# Sensors.net
KiCad netlist of a schematic drawn in Altium Designer
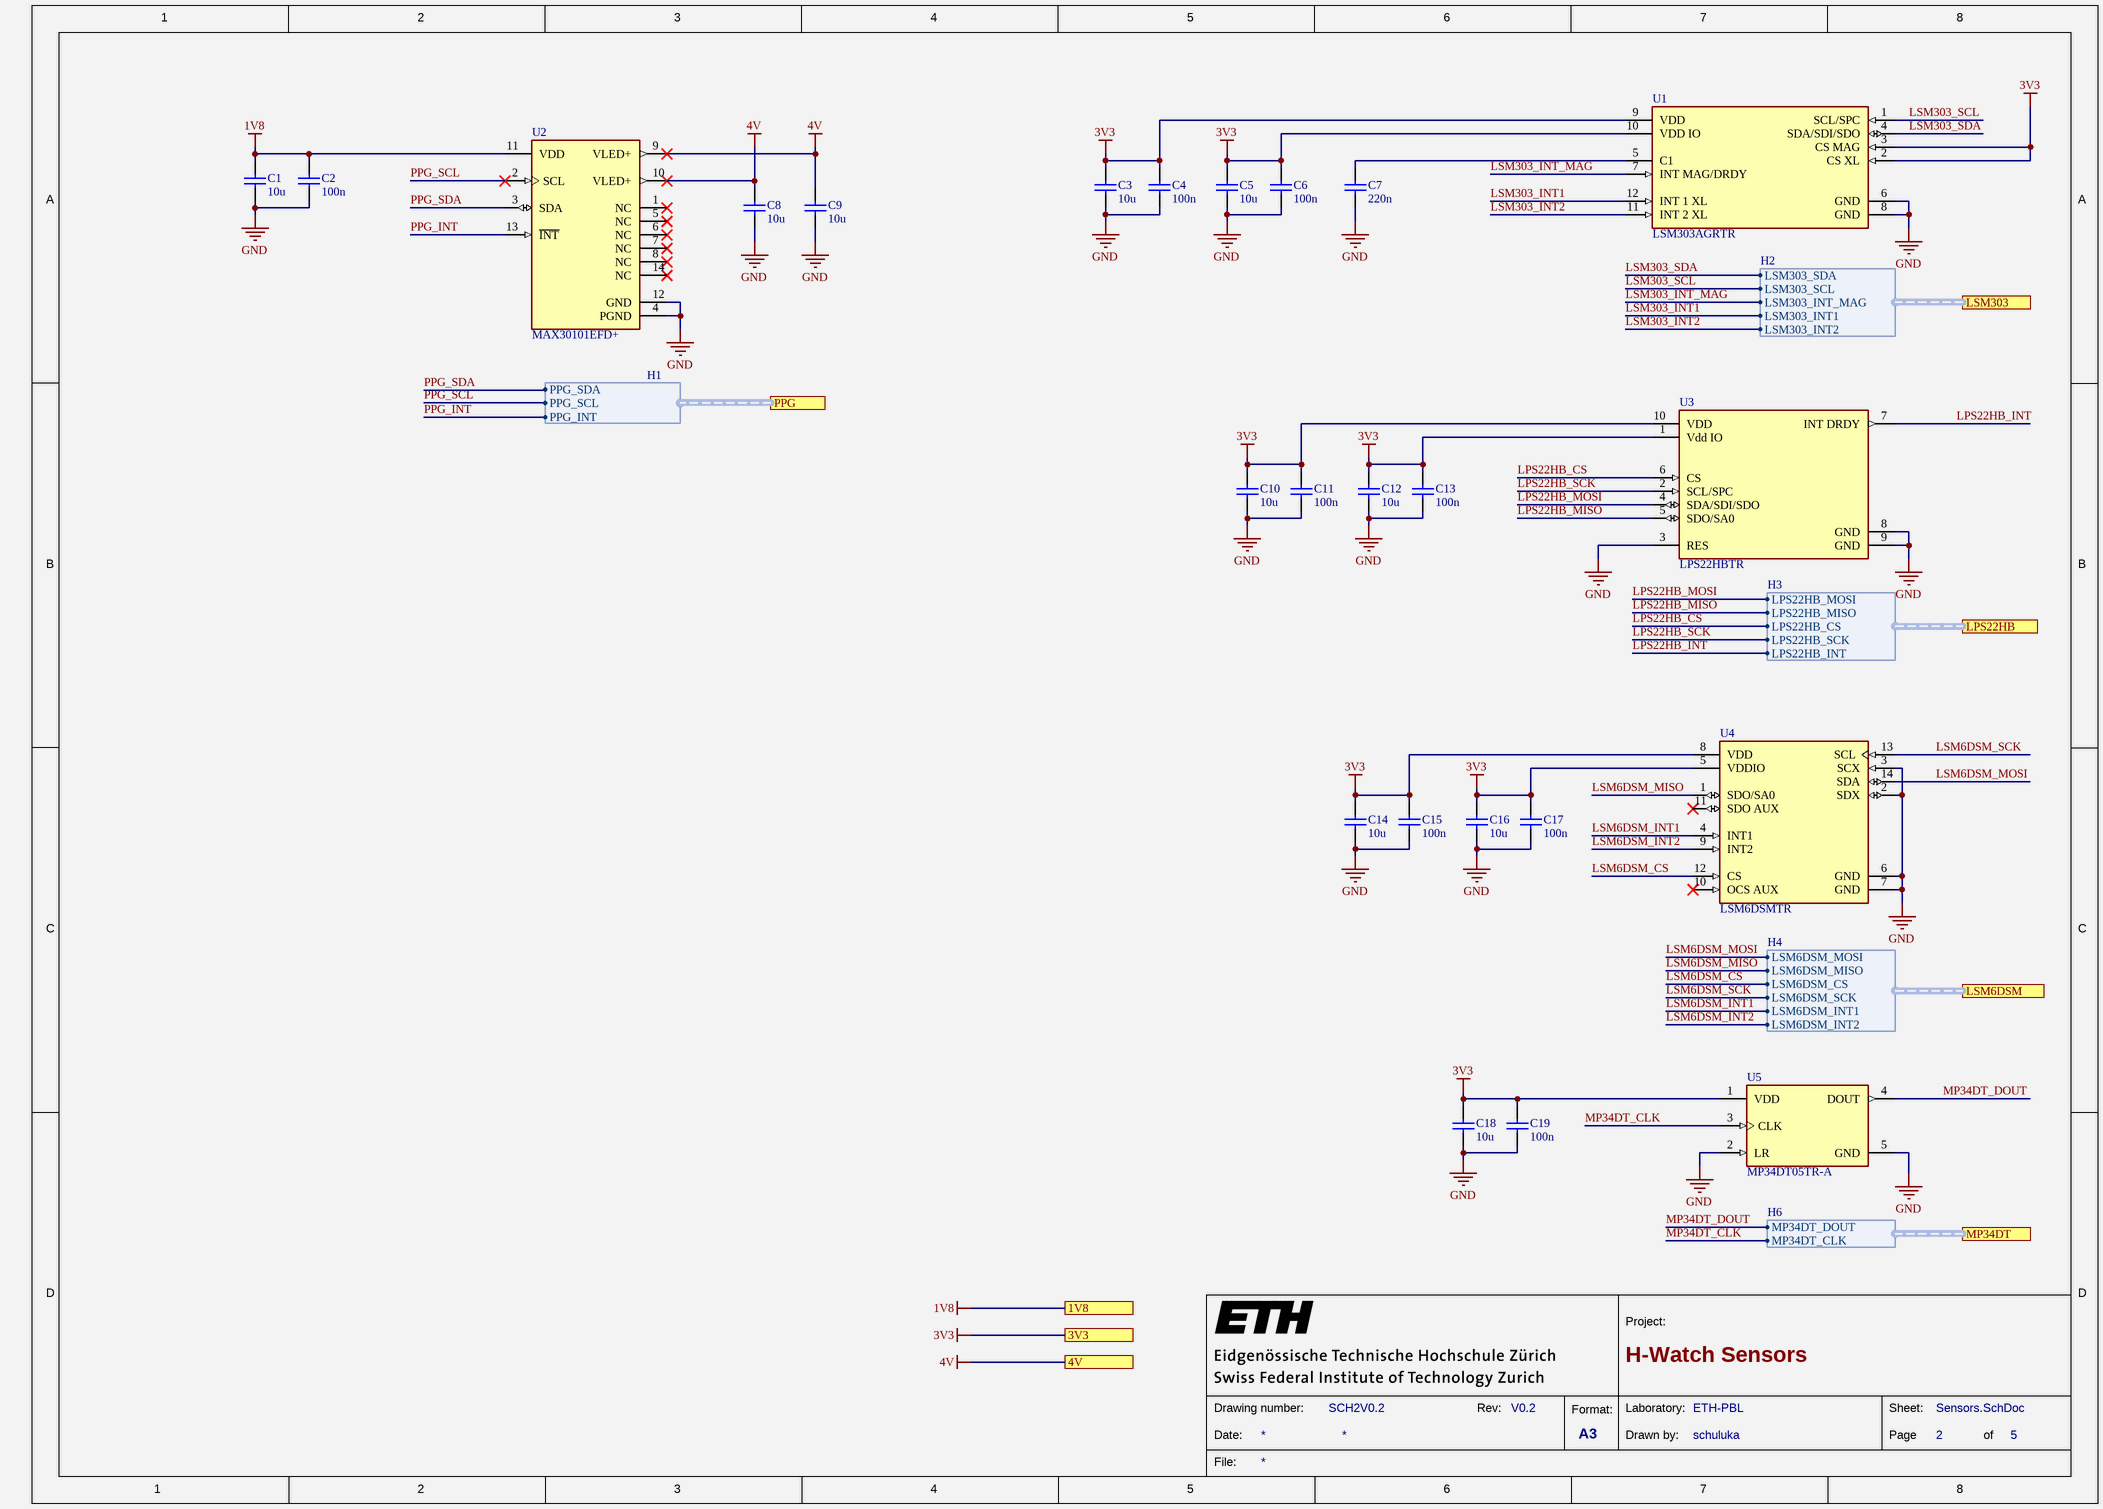
[diagram p0: Sensors.SchDoc]

(export (version "E")
  (design (tool "Eeschema 10.0.6"))
  (components
    (comp (ref "C1")
      (value "10u")
      (footprint "CAPC1005X70X10NL05")
      (description "Chip Capacitor, 10 uF, +/- 20%, -55 to 85 degC, 0402 (1005 Metric), RoHS, Tape and Reel")
      (fields
        (field (name "PCN PART NUMBER") "MLCCPartNumberChange30/Nov/2012")
        (field (name "TOLERANCE") "±20%")
      )
      (libsource (lib "Altium Content Vault") (part "CAP-NP-2"))
    )
    (comp (ref "C2")
      (value "100n")
      (footprint "CAPC1005X60X30ML05T10")
      (fields (field (name "MANUFACTURER") "Kemet") (field (name "PART NUMBER") "C0402C104K8PACTU"))
      (libsource (lib "Altium Content Vault") (part "CAP"))
    )
    (comp (ref "C3")
      (value "10u")
      (footprint "CAPC1005X70X10NL05")
      (description "Chip Capacitor, 10 uF, +/- 20%, -55 to 85 degC, 0402 (1005 Metric), RoHS, Tape and Reel")
      (fields
        (field (name "PCN PART NUMBER") "MLCCPartNumberChange30/Nov/2012")
        (field (name "TOLERANCE") "±20%")
      )
      (libsource (lib "Altium Content Vault") (part "CAP-NP-2"))
    )
    (comp (ref "C4")
      (value "100n")
      (footprint "CAPC1005X60X30ML05T10")
      (fields (field (name "MANUFACTURER") "Kemet") (field (name "PART NUMBER") "C0402C104K8PACTU"))
      (libsource (lib "Altium Content Vault") (part "CAP"))
    )
    (comp (ref "C5")
      (value "10u")
      (footprint "CAPC1005X70X10NL05")
      (description "Chip Capacitor, 10 uF, +/- 20%, -55 to 85 degC, 0402 (1005 Metric), RoHS, Tape and Reel")
      (fields
        (field (name "PCN PART NUMBER") "MLCCPartNumberChange30/Nov/2012")
        (field (name "TOLERANCE") "±20%")
      )
      (libsource (lib "Altium Content Vault") (part "CAP-NP-2"))
    )
    (comp (ref "C6")
      (value "100n")
      (footprint "CAPC1005X60X30ML05T10")
      (fields (field (name "MANUFACTURER") "Kemet") (field (name "PART NUMBER") "C0402C104K8PACTU"))
      (libsource (lib "Altium Content Vault") (part "CAP"))
    )
    (comp (ref "C7")
      (value "220n")
      (footprint "CAPC1005X55X25ML05T10")
      (description "Chip Capacitor, 220 nF, +/- 10%, 16 V, -55 to 125 degC, 0402 (1005 Metric), RoHS, Tape and Reel")
      (fields (field (name "MANUFACTURER") "Murata"))
      (libsource (lib "Altium Content Vault") (part "CAP-NP-2"))
    )
    (comp (ref "C8")
      (value "10u")
      (footprint "CAPC1005X70X10NL05")
      (description "Chip Capacitor, 10 uF, +/- 20%, -55 to 85 degC, 0402 (1005 Metric), RoHS, Tape and Reel")
      (fields
        (field (name "PCN PART NUMBER") "MLCCPartNumberChange30/Nov/2012")
        (field (name "TOLERANCE") "±20%")
      )
      (libsource (lib "Altium Content Vault") (part "CAP-NP-2"))
    )
    (comp (ref "C9")
      (value "10u")
      (footprint "CAPC1005X70X10NL05")
      (description "Chip Capacitor, 10 uF, +/- 20%, -55 to 85 degC, 0402 (1005 Metric), RoHS, Tape and Reel")
      (fields
        (field (name "PCN PART NUMBER") "MLCCPartNumberChange30/Nov/2012")
        (field (name "TOLERANCE") "±20%")
      )
      (libsource (lib "Altium Content Vault") (part "CAP-NP-2"))
    )
    (comp (ref "C10")
      (value "10u")
      (footprint "CAPC1005X70X10NL05")
      (description "Chip Capacitor, 10 uF, +/- 20%, -55 to 85 degC, 0402 (1005 Metric), RoHS, Tape and Reel")
      (fields
        (field (name "PCN PART NUMBER") "MLCCPartNumberChange30/Nov/2012")
        (field (name "TOLERANCE") "±20%")
      )
      (libsource (lib "Altium Content Vault") (part "CAP-NP-2"))
    )
    (comp (ref "C11")
      (value "100n")
      (footprint "CAPC1005X60X30ML05T10")
      (fields (field (name "MANUFACTURER") "Kemet") (field (name "PART NUMBER") "C0402C104K8PACTU"))
      (libsource (lib "Altium Content Vault") (part "CAP"))
    )
    (comp (ref "C12")
      (value "10u")
      (footprint "CAPC1005X70X10NL05")
      (description "Chip Capacitor, 10 uF, +/- 20%, -55 to 85 degC, 0402 (1005 Metric), RoHS, Tape and Reel")
      (fields
        (field (name "PCN PART NUMBER") "MLCCPartNumberChange30/Nov/2012")
        (field (name "TOLERANCE") "±20%")
      )
      (libsource (lib "Altium Content Vault") (part "CAP-NP-2"))
    )
    (comp (ref "C13")
      (value "100n")
      (footprint "CAPC1005X60X30ML05T10")
      (fields (field (name "MANUFACTURER") "Kemet") (field (name "PART NUMBER") "C0402C104K8PACTU"))
      (libsource (lib "Altium Content Vault") (part "CAP"))
    )
    (comp (ref "C14")
      (value "10u")
      (footprint "CAPC1005X70X10NL05")
      (description "Chip Capacitor, 10 uF, +/- 20%, -55 to 85 degC, 0402 (1005 Metric), RoHS, Tape and Reel")
      (fields
        (field (name "PCN PART NUMBER") "MLCCPartNumberChange30/Nov/2012")
        (field (name "TOLERANCE") "±20%")
      )
      (libsource (lib "Altium Content Vault") (part "CAP-NP-2"))
    )
    (comp (ref "C15")
      (value "100n")
      (footprint "CAPC1005X60X30ML05T10")
      (fields (field (name "MANUFACTURER") "Kemet") (field (name "PART NUMBER") "C0402C104K8PACTU"))
      (libsource (lib "Altium Content Vault") (part "CAP"))
    )
    (comp (ref "C16")
      (value "10u")
      (footprint "CAPC1005X70X10NL05")
      (description "Chip Capacitor, 10 uF, +/- 20%, -55 to 85 degC, 0402 (1005 Metric), RoHS, Tape and Reel")
      (fields
        (field (name "PCN PART NUMBER") "MLCCPartNumberChange30/Nov/2012")
        (field (name "TOLERANCE") "±20%")
      )
      (libsource (lib "Altium Content Vault") (part "CAP-NP-2"))
    )
    (comp (ref "C17")
      (value "100n")
      (footprint "CAPC1005X60X30ML05T10")
      (fields (field (name "MANUFACTURER") "Kemet") (field (name "PART NUMBER") "C0402C104K8PACTU"))
      (libsource (lib "Altium Content Vault") (part "CAP"))
    )
    (comp (ref "C18")
      (value "10u")
      (footprint "CAPC1005X70X10NL05")
      (description "Chip Capacitor, 10 uF, +/- 20%, -55 to 85 degC, 0402 (1005 Metric), RoHS, Tape and Reel")
      (fields
        (field (name "PCN PART NUMBER") "MLCCPartNumberChange30/Nov/2012")
        (field (name "TOLERANCE") "±20%")
      )
      (libsource (lib "Altium Content Vault") (part "CAP-NP-2"))
    )
    (comp (ref "C19")
      (value "100n")
      (footprint "CAPC1005X60X30ML05T10")
      (fields (field (name "MANUFACTURER") "Kemet") (field (name "PART NUMBER") "C0402C104K8PACTU"))
      (libsource (lib "Altium Content Vault") (part "CAP"))
    )
    (comp (ref "U1")
      (value "LSM303AGRTR")
      (footprint "FP-LGA-12-8487206-MFG")
      (description "IMU ACCEL/MAG I2C/SPI 12LGA")
      (fields
        (field (name "OCTOPART") "https://octopart.com/lsm303agrtr-stmicroelectronics-59386630")
        (field (name "MANUFACTURER") "STMicroelectronics")
      )
      (libsource (lib "Altium Content Vault") (part "dfb71b4f0b3d4bd25037e938b2e7b05"))
    )
    (comp (ref "U2")
      (value "MAX30101EFD+")
      (footprint "FP-F143A5-1-MFG")
      (description "INTEGRATED OPTICAL SENSOR")
      (fields
        (field (name "MANUFACTURER") "Maxim Integrated")
        (field (name "OCTOPART") "https://octopart.com/max30101efd%2B-maxim+integrated-57054333")
      )
      (libsource (lib "Altium Content Vault") (part "7412f82398c18c21c59cad441ae59a4"))
    )
    (comp (ref "U3")
      (value "LPS22HBTR")
      (footprint "FP-HLGA-10L-8479831-0")
      (description "MEMS NANO PRESSURE SENSOR: 260-1")
      (fields
        (field (name "OCTOPART") "https://octopart.com/lps22hbtr-stmicroelectronics-51851131")
        (field (name "MANUFACTURER") "STMicroelectronics")
      )
      (libsource (lib "Altium Content Vault") (part "d4c28707ea3ba579869663dd93796c5"))
    )
    (comp (ref "U4")
      (value "LSM6DSMTR")
      (footprint "FP-LGA-14L-DM00249496-MFG")
      (description "IMU ACCEL/GYRO I2C/SPI 14LGA")
      (fields
        (field (name "OCTOPART") "https://octopart.com/lsm6dsmtr-stmicroelectronics-66358194")
        (field (name "MANUFACTURER") "STMicroelectronics")
      )
      (libsource (lib "Altium Content Vault") (part "dd82ae232bae541fa9c740d21cb9072"))
    )
    (comp (ref "U5")
      (value "MP34DT05TR-A")
      (footprint "FP-HCLGA-DM00231908-MFG")
      (description "MEMS AUD MIC SENSOR OMNI 4HCLGA")
      (fields
        (field (name "OCTOPART") "https://octopart.com/mp34dt05tr-a-stmicroelectronics-87879016")
        (field (name "MANUFACTURER") "STMicroelectronics")
      )
      (libsource (lib "Altium Content Vault") (part "b42018b50dcec9466a4e70146be022e"))
    )
  )
  (nets
    (net (code "7") (name "/LPS22HB_CS") (class "Default")
      (node (ref "U3") (pin "6") (pinfunction "CS_6") (pintype "input"))
    )
    (net (code "8") (name "/LPS22HB_INT") (class "Default")
      (node (ref "U3") (pin "7") (pinfunction "INT_DRDY_7") (pintype "output"))
    )
    (net (code "9") (name "/LPS22HB_MISO") (class "Default")
      (node (ref "U3") (pin "5") (pinfunction "SDO/SA0_5") (pintype "bidirectional"))
    )
    (net (code "10") (name "/LPS22HB_MOSI") (class "Default")
      (node (ref "U3") (pin "4") (pinfunction "SDA/SDI/SDO_4") (pintype "bidirectional"))
    )
    (net (code "11") (name "/LPS22HB_SCK") (class "Default")
      (node (ref "U3") (pin "2") (pinfunction "SCL/SPC_2") (pintype "input"))
    )
    (net (code "12") (name "/LSM6DSM_CS") (class "Default")
      (node (ref "U4") (pin "12") (pinfunction "CS_12") (pintype "input"))
    )
    (net (code "13") (name "/LSM6DSM_INT1") (class "Default")
      (node (ref "U4") (pin "4") (pinfunction "INT1_4") (pintype "input"))
    )
    (net (code "14") (name "/LSM6DSM_INT2") (class "Default")
      (node (ref "U4") (pin "9") (pinfunction "INT2_9") (pintype "input"))
    )
    (net (code "15") (name "/LSM6DSM_MISO") (class "Default")
      (node (ref "U4") (pin "1") (pinfunction "SDO/SA0_1") (pintype "bidirectional"))
    )
    (net (code "16") (name "/LSM6DSM_MOSI") (class "Default")
      (node (ref "U4") (pin "14") (pinfunction "SDA_14") (pintype "bidirectional"))
    )
    (net (code "17") (name "/LSM6DSM_SCK") (class "Default")
      (node (ref "U4") (pin "13") (pinfunction "SCL_13") (pintype "input"))
    )
    (net (code "18") (name "/LSM303_INT1") (class "Default")
      (node (ref "U1") (pin "12") (pinfunction "INT_1_XL_12") (pintype "input"))
    )
    (net (code "19") (name "/LSM303_INT2") (class "Default")
      (node (ref "U1") (pin "11") (pinfunction "INT_2_XL_11") (pintype "input"))
    )
    (net (code "20") (name "/LSM303_INT_MAG") (class "Default")
      (node (ref "U1") (pin "7") (pinfunction "INT_MAG/DRDY_7") (pintype "input"))
    )
    (net (code "21") (name "/LSM303_SCL") (class "Default")
      (node (ref "U1") (pin "1") (pinfunction "SCL/SPC_1") (pintype "input"))
    )
    (net (code "22") (name "/LSM303_SDA") (class "Default")
      (node (ref "U1") (pin "4") (pinfunction "SDA/SDI/SDO_4") (pintype "bidirectional"))
    )
    (net (code "23") (name "/MP34DT_CLK") (class "Default")
      (node (ref "U5") (pin "3") (pinfunction "CLK_3") (pintype "input"))
    )
    (net (code "24") (name "/MP34DT_DOUT") (class "Default")
      (node (ref "U5") (pin "4") (pinfunction "DOUT_4") (pintype "output"))
    )
    (net (code "25") (name "/PPG_INT") (class "Default")
      (node (ref "U2") (pin "13") (pinfunction "~{INT}_13") (pintype "input"))
    )
    (net (code "26") (name "/PPG_SCL") (class "Default")
      (node (ref "U2") (pin "2") (pinfunction "SCL_2") (pintype "input+no_connect"))
    )
    (net (code "27") (name "/PPG_SDA") (class "Default")
      (node (ref "U2") (pin "3") (pinfunction "SDA_3") (pintype "bidirectional"))
    )
    (net (code "33") (name "1V8") (class "Default")
      (node (ref "C1") (pin "2") (pinfunction "2_2") (pintype "passive"))
      (node (ref "C2") (pin "2") (pinfunction "2_2") (pintype "passive"))
      (node (ref "U2") (pin "11") (pinfunction "VDD_11") (pintype "power_in"))
    )
    (net (code "34") (name "3V3") (class "Default")
      (node (ref "C10") (pin "2") (pinfunction "2_2") (pintype "passive"))
      (node (ref "C11") (pin "2") (pinfunction "2_2") (pintype "passive"))
      (node (ref "C12") (pin "2") (pinfunction "2_2") (pintype "passive"))
      (node (ref "C13") (pin "2") (pinfunction "2_2") (pintype "passive"))
      (node (ref "C14") (pin "2") (pinfunction "2_2") (pintype "passive"))
      (node (ref "C15") (pin "2") (pinfunction "2_2") (pintype "passive"))
      (node (ref "C16") (pin "2") (pinfunction "2_2") (pintype "passive"))
      (node (ref "C17") (pin "2") (pinfunction "2_2") (pintype "passive"))
      (node (ref "C18") (pin "2") (pinfunction "2_2") (pintype "passive"))
      (node (ref "C19") (pin "2") (pinfunction "2_2") (pintype "passive"))
      (node (ref "C3") (pin "2") (pinfunction "2_2") (pintype "passive"))
      (node (ref "C4") (pin "2") (pinfunction "2_2") (pintype "passive"))
      (node (ref "C5") (pin "2") (pinfunction "2_2") (pintype "passive"))
      (node (ref "C6") (pin "2") (pinfunction "2_2") (pintype "passive"))
      (node (ref "U1") (pin "10") (pinfunction "VDD_IO_10") (pintype "power_in"))
      (node (ref "U1") (pin "2") (pinfunction "CS_XL_2") (pintype "input"))
      (node (ref "U1") (pin "3") (pinfunction "CS_MAG_3") (pintype "input"))
      (node (ref "U1") (pin "9") (pinfunction "VDD_9") (pintype "power_in"))
      (node (ref "U3") (pin "1") (pinfunction "Vdd_IO_1") (pintype "power_in"))
      (node (ref "U3") (pin "10") (pinfunction "VDD_10") (pintype "power_in"))
      (node (ref "U4") (pin "5") (pinfunction "VDDIO_5") (pintype "power_in"))
      (node (ref "U4") (pin "8") (pinfunction "VDD_8") (pintype "power_in"))
      (node (ref "U5") (pin "1") (pinfunction "VDD_1") (pintype "power_in"))
    )
    (net (code "35") (name "4V") (class "Default")
      (node (ref "C8") (pin "2") (pinfunction "2_2") (pintype "passive"))
      (node (ref "C9") (pin "2") (pinfunction "2_2") (pintype "passive"))
      (node (ref "U2") (pin "10") (pinfunction "VLED+_10") (pintype "output"))
      (node (ref "U2") (pin "9") (pinfunction "VLED+_9") (pintype "output"))
    )
    (net (code "36") (name "GND") (class "Default")
      (node (ref "C1") (pin "1") (pinfunction "1_1") (pintype "passive"))
      (node (ref "C10") (pin "1") (pinfunction "1_1") (pintype "passive"))
      (node (ref "C11") (pin "1") (pinfunction "1_1") (pintype "passive"))
      (node (ref "C12") (pin "1") (pinfunction "1_1") (pintype "passive"))
      (node (ref "C13") (pin "1") (pinfunction "1_1") (pintype "passive"))
      (node (ref "C14") (pin "1") (pinfunction "1_1") (pintype "passive"))
      (node (ref "C15") (pin "1") (pinfunction "1_1") (pintype "passive"))
      (node (ref "C16") (pin "1") (pinfunction "1_1") (pintype "passive"))
      (node (ref "C17") (pin "1") (pinfunction "1_1") (pintype "passive"))
      (node (ref "C18") (pin "1") (pinfunction "1_1") (pintype "passive"))
      (node (ref "C19") (pin "1") (pinfunction "1_1") (pintype "passive"))
      (node (ref "C2") (pin "1") (pinfunction "1_1") (pintype "passive"))
      (node (ref "C3") (pin "1") (pinfunction "1_1") (pintype "passive"))
      (node (ref "C4") (pin "1") (pinfunction "1_1") (pintype "passive"))
      (node (ref "C5") (pin "1") (pinfunction "1_1") (pintype "passive"))
      (node (ref "C6") (pin "1") (pinfunction "1_1") (pintype "passive"))
      (node (ref "C7") (pin "1") (pinfunction "1_1") (pintype "passive"))
      (node (ref "C8") (pin "1") (pinfunction "1_1") (pintype "passive"))
      (node (ref "C9") (pin "1") (pinfunction "1_1") (pintype "passive"))
      (node (ref "U1") (pin "6") (pinfunction "GND_6") (pintype "power_in"))
      (node (ref "U1") (pin "8") (pinfunction "GND_8") (pintype "power_in"))
      (node (ref "U2") (pin "12") (pinfunction "GND_12") (pintype "power_in"))
      (node (ref "U2") (pin "4") (pinfunction "PGND_4") (pintype "power_in"))
      (node (ref "U3") (pin "3") (pinfunction "RES_3") (pintype "passive"))
      (node (ref "U3") (pin "8") (pinfunction "GND_8") (pintype "power_in"))
      (node (ref "U3") (pin "9") (pinfunction "GND_9") (pintype "power_in"))
      (node (ref "U4") (pin "2") (pinfunction "SDX_2") (pintype "bidirectional"))
      (node (ref "U4") (pin "3") (pinfunction "SCX_3") (pintype "input"))
      (node (ref "U4") (pin "6") (pinfunction "GND_6") (pintype "power_in"))
      (node (ref "U4") (pin "7") (pinfunction "GND_7") (pintype "power_in"))
      (node (ref "U5") (pin "2") (pinfunction "LR_2") (pintype "input"))
      (node (ref "U5") (pin "5") (pinfunction "GND_5") (pintype "power_in"))
    )
    (net (code "37") (name "Net-(U1-C1)") (class "Default")
      (node (ref "C7") (pin "2") (pinfunction "2_2") (pintype "passive"))
      (node (ref "U1") (pin "5") (pinfunction "C1_5") (pintype "passive"))
    )
    (net (code "38") (name "unconnected-(U2-NC-Pad1)") (class "Default")
      (node (ref "U2") (pin "1") (pinfunction "NC_1") (pintype "passive+no_connect"))
    )
    (net (code "39") (name "unconnected-(U2-NC-Pad5)") (class "Default")
      (node (ref "U2") (pin "5") (pinfunction "NC_5") (pintype "passive+no_connect"))
    )
    (net (code "40") (name "unconnected-(U2-NC-Pad6)") (class "Default")
      (node (ref "U2") (pin "6") (pinfunction "NC_6") (pintype "passive+no_connect"))
    )
    (net (code "41") (name "unconnected-(U2-NC-Pad7)") (class "Default")
      (node (ref "U2") (pin "7") (pinfunction "NC_7") (pintype "passive+no_connect"))
    )
    (net (code "42") (name "unconnected-(U2-NC-Pad8)") (class "Default")
      (node (ref "U2") (pin "8") (pinfunction "NC_8") (pintype "passive+no_connect"))
    )
    (net (code "43") (name "unconnected-(U2-NC-Pad14)") (class "Default")
      (node (ref "U2") (pin "14") (pinfunction "NC_14") (pintype "passive+no_connect"))
    )
    (net (code "44") (name "unconnected-(U4-OCS_AUX-Pad10)") (class "Default")
      (node (ref "U4") (pin "10") (pinfunction "OCS_AUX_10") (pintype "input+no_connect"))
    )
    (net (code "45") (name "unconnected-(U4-SDO_AUX-Pad11)") (class "Default")
      (node (ref "U4") (pin "11") (pinfunction "SDO_AUX_11") (pintype "bidirectional+no_connect"))
    )
  )
)
